# bottom.net
KiCad netlist of a schematic drawn in EAGLE
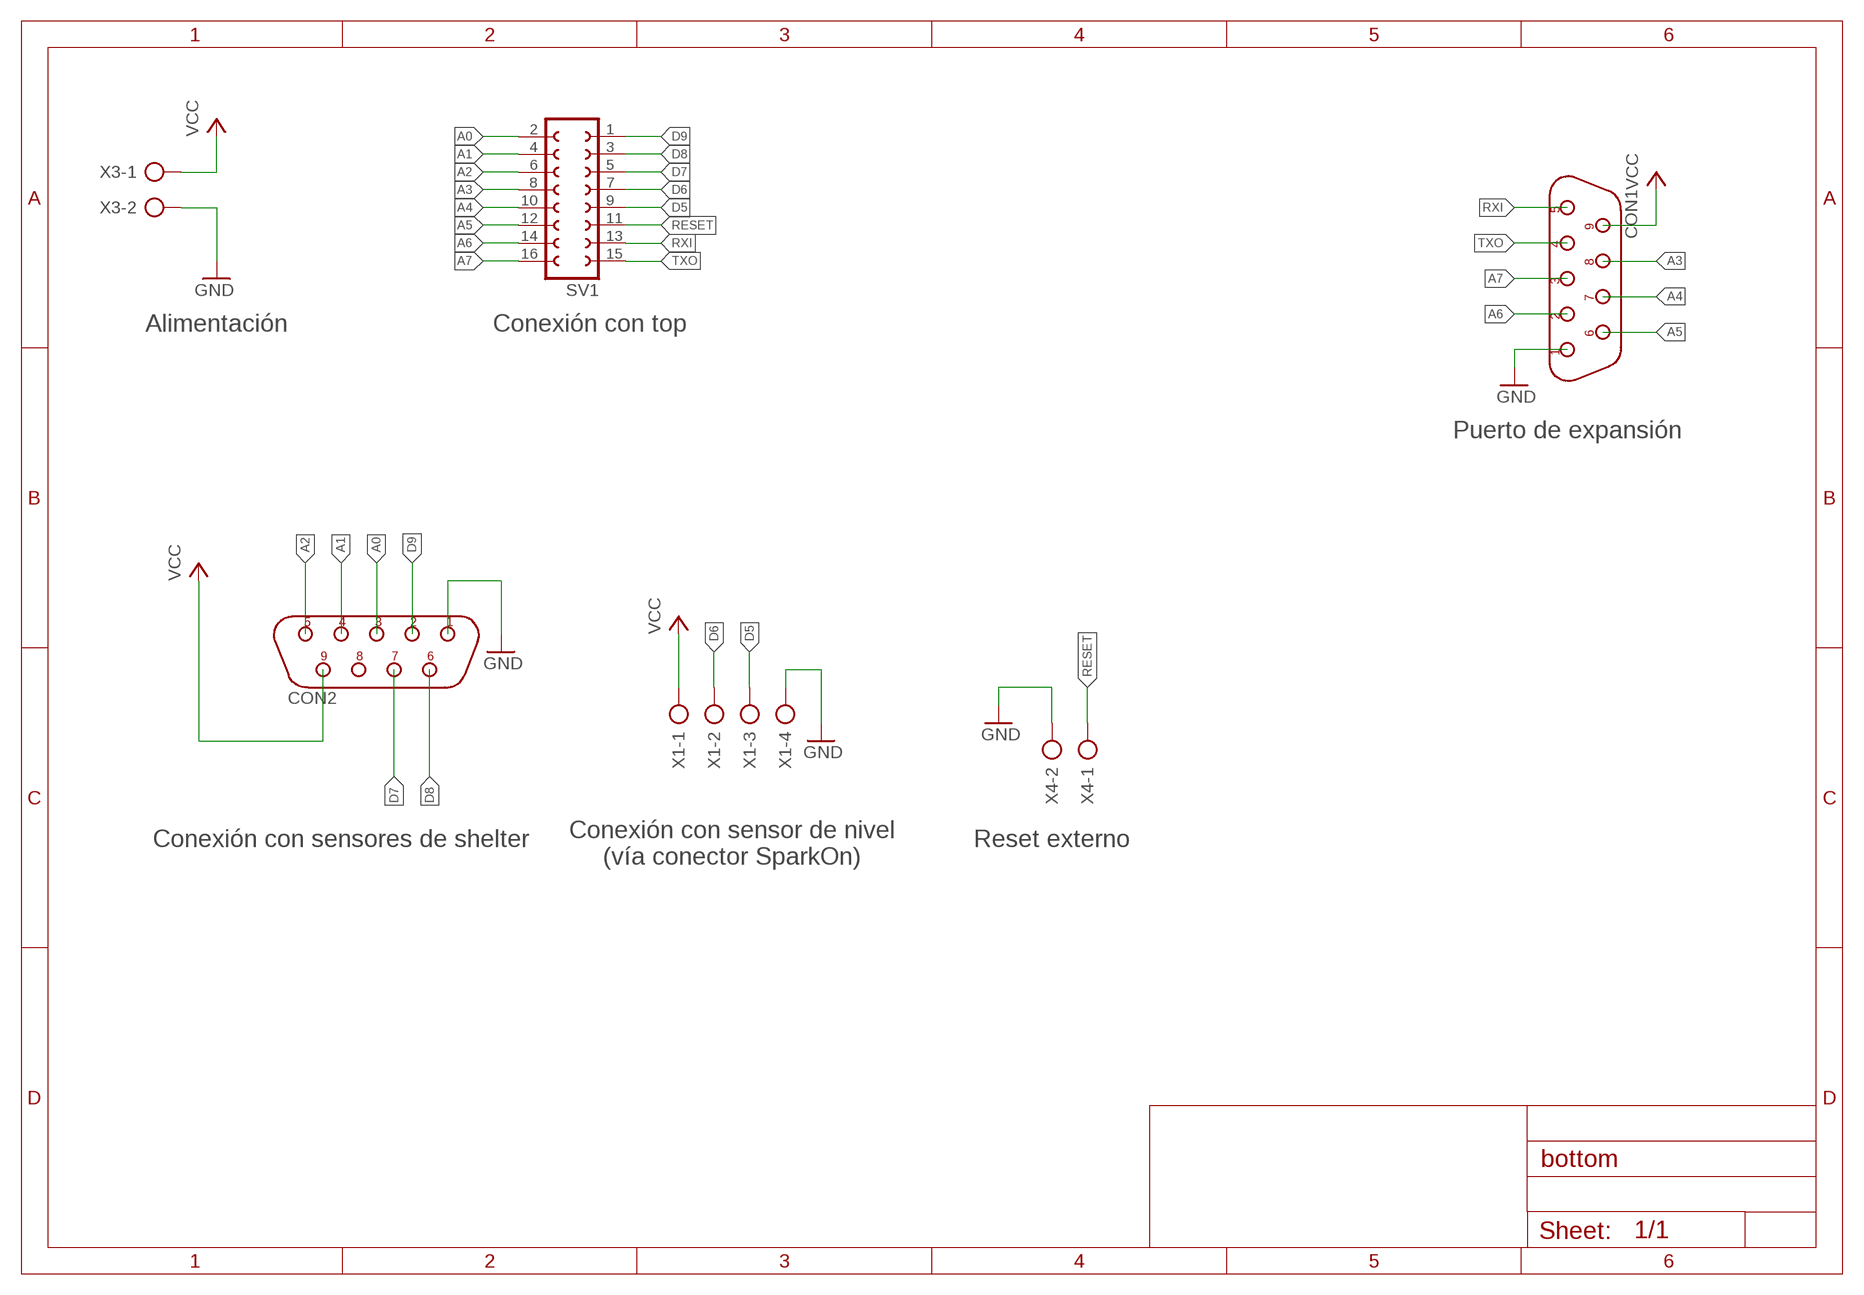
[diagram p0: schematic, sheet 1]

(export (version "E")
  (design (tool "Eeschema 10.0.6"))
  (components
    (comp (ref "CON1")
      (value "DB9M/90")
      (footprint "eagle-import:D-09M_90")
      (libsource (lib "eagle-import") (part "DB9M/90"))
    )
    (comp (ref "CON2")
      (value "DB9M/90")
      (footprint "eagle-import:D-09M_90")
      (libsource (lib "eagle-import") (part "DB9M/90"))
    )
    (comp (ref "SV1")
      (value "FE08-2")
      (footprint "eagle-import:FE08-2")
      (libsource (lib "eagle-import") (part "FE08-2"))
    )
    (comp (ref "X1")
      (value "AK500/4")
      (footprint "eagle-import:AK500_4")
      (libsource (lib "eagle-import") (part "AK500/4"))
    )
    (comp (ref "X3")
      (value "AK500/2")
      (footprint "eagle-import:AK500_2")
      (libsource (lib "eagle-import") (part "AK500/2"))
    )
    (comp (ref "X4")
      (value "AK500/2")
      (footprint "eagle-import:AK500_2")
      (libsource (lib "eagle-import") (part "AK500/2"))
    )
  )
  (nets
    (net (code "1") (name "A0") (class "Default")
      (node (ref "CON2") (pin "3") (pinfunction "3_3") (pintype "passive"))
      (node (ref "SV1") (pin "2") (pinfunction "2_2") (pintype "passive"))
    )
    (net (code "2") (name "A1") (class "Default")
      (node (ref "CON2") (pin "4") (pinfunction "4_4") (pintype "passive"))
      (node (ref "SV1") (pin "4") (pinfunction "4_4") (pintype "passive"))
    )
    (net (code "3") (name "A2") (class "Default")
      (node (ref "CON2") (pin "5") (pinfunction "5_5") (pintype "passive"))
      (node (ref "SV1") (pin "6") (pinfunction "6_6") (pintype "passive"))
    )
    (net (code "4") (name "A3") (class "Default")
      (node (ref "CON1") (pin "8") (pinfunction "8_8") (pintype "passive"))
      (node (ref "SV1") (pin "8") (pinfunction "8_8") (pintype "passive"))
    )
    (net (code "5") (name "A4") (class "Default")
      (node (ref "CON1") (pin "7") (pinfunction "7_7") (pintype "passive"))
      (node (ref "SV1") (pin "10") (pinfunction "10_10") (pintype "passive"))
    )
    (net (code "6") (name "A5") (class "Default")
      (node (ref "CON1") (pin "6") (pinfunction "6_6") (pintype "passive"))
      (node (ref "SV1") (pin "12") (pinfunction "12_12") (pintype "passive"))
    )
    (net (code "7") (name "A6") (class "Default")
      (node (ref "CON1") (pin "2") (pinfunction "2_2") (pintype "passive"))
      (node (ref "SV1") (pin "14") (pinfunction "14_14") (pintype "passive"))
    )
    (net (code "8") (name "A7") (class "Default")
      (node (ref "CON1") (pin "3") (pinfunction "3_3") (pintype "passive"))
      (node (ref "SV1") (pin "16") (pinfunction "16_16") (pintype "passive"))
    )
    (net (code "9") (name "D5") (class "Default")
      (node (ref "SV1") (pin "9") (pinfunction "9_9") (pintype "passive"))
      (node (ref "X1") (pin "3") (pinfunction "KL_3") (pintype "passive"))
    )
    (net (code "10") (name "D6") (class "Default")
      (node (ref "SV1") (pin "7") (pinfunction "7_7") (pintype "passive"))
      (node (ref "X1") (pin "2") (pinfunction "KL_2") (pintype "passive"))
    )
    (net (code "11") (name "D7") (class "Default")
      (node (ref "CON2") (pin "7") (pinfunction "7_7") (pintype "passive"))
      (node (ref "SV1") (pin "5") (pinfunction "5_5") (pintype "passive"))
    )
    (net (code "12") (name "D8") (class "Default")
      (node (ref "CON2") (pin "6") (pinfunction "6_6") (pintype "passive"))
      (node (ref "SV1") (pin "3") (pinfunction "3_3") (pintype "passive"))
    )
    (net (code "13") (name "D9") (class "Default")
      (node (ref "CON2") (pin "2") (pinfunction "2_2") (pintype "passive"))
      (node (ref "SV1") (pin "1") (pinfunction "1_1") (pintype "passive"))
    )
    (net (code "14") (name "GND") (class "Default")
      (node (ref "CON1") (pin "1") (pinfunction "1_1") (pintype "passive"))
      (node (ref "CON2") (pin "1") (pinfunction "1_1") (pintype "passive"))
      (node (ref "X1") (pin "4") (pinfunction "KL_4") (pintype "passive"))
      (node (ref "X3") (pin "2") (pinfunction "KL_2") (pintype "passive"))
      (node (ref "X4") (pin "2") (pinfunction "KL_2") (pintype "passive"))
    )
    (net (code "15") (name "RESET") (class "Default")
      (node (ref "SV1") (pin "11") (pinfunction "11_11") (pintype "passive"))
      (node (ref "X4") (pin "1") (pinfunction "KL_1") (pintype "passive"))
    )
    (net (code "16") (name "RXI") (class "Default")
      (node (ref "CON1") (pin "5") (pinfunction "5_5") (pintype "passive"))
      (node (ref "SV1") (pin "13") (pinfunction "13_13") (pintype "passive"))
    )
    (net (code "17") (name "TXO") (class "Default")
      (node (ref "CON1") (pin "4") (pinfunction "4_4") (pintype "passive"))
      (node (ref "SV1") (pin "15") (pinfunction "15_15") (pintype "passive"))
    )
    (net (code "18") (name "VCC") (class "Default")
      (node (ref "CON1") (pin "9") (pinfunction "9_9") (pintype "passive"))
      (node (ref "CON2") (pin "9") (pinfunction "9_9") (pintype "passive"))
      (node (ref "X1") (pin "1") (pinfunction "KL_1") (pintype "passive"))
      (node (ref "X3") (pin "1") (pinfunction "KL_1") (pintype "passive"))
    )
    (net (code "19") (name "unconnected-(CON2-Pad8)") (class "Default")
      (node (ref "CON2") (pin "8") (pinfunction "8_8") (pintype "passive"))
    )
  )
)
